# power.net
KiCad netlist of a schematic drawn in Altium Designer
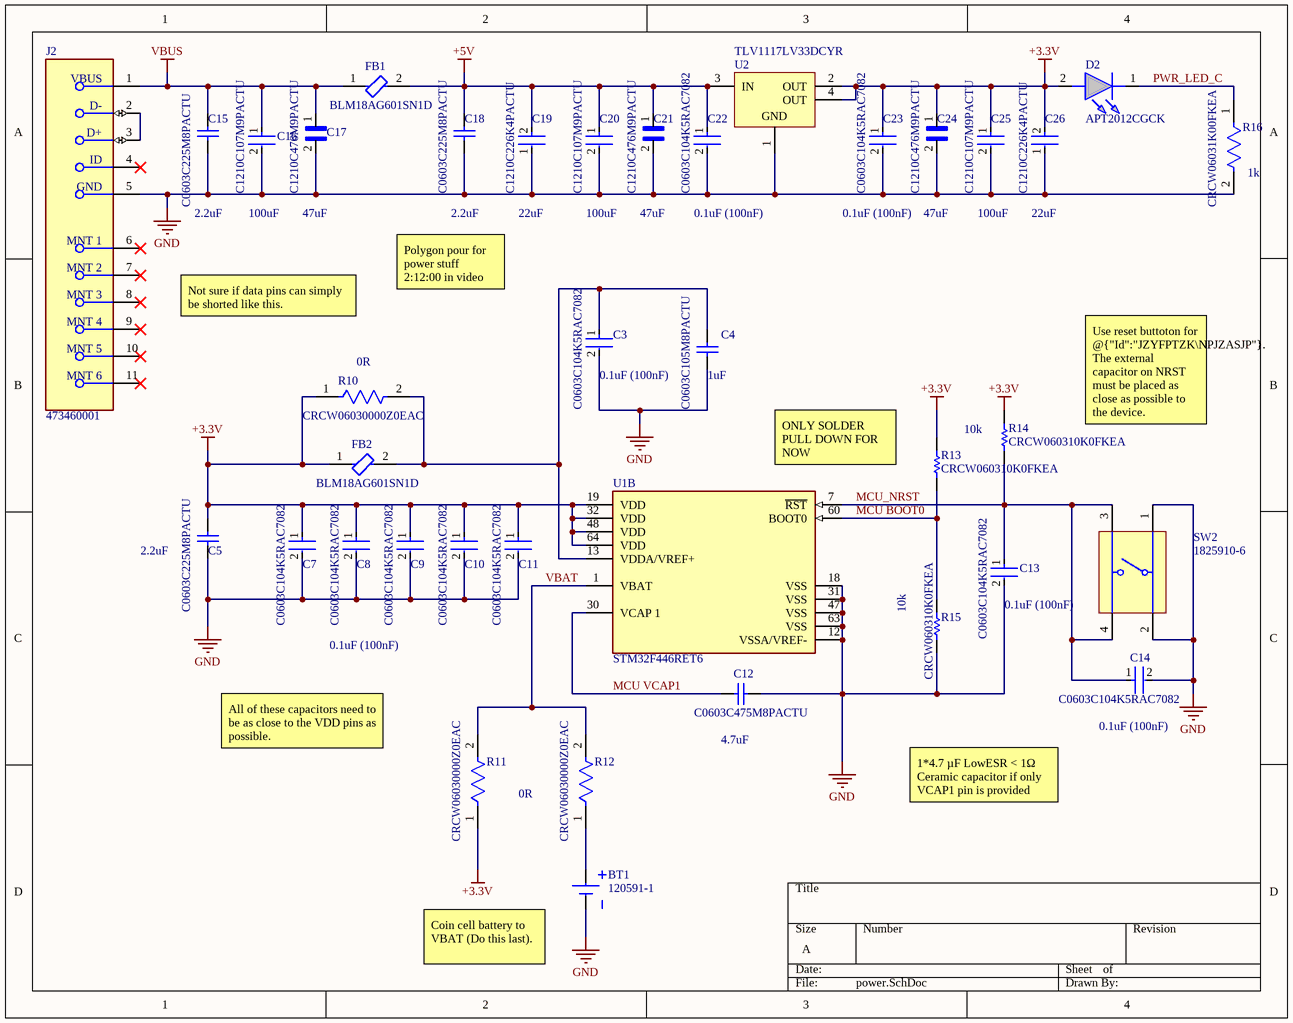
[diagram p0: power.SchDoc]

(export (version "E")
  (design (tool "Eeschema 10.0.6"))
  (components
    (comp (ref "BT1")
      (value "120591-1")
      (footprint "TECO-120591-1-2_V")
      (description "Lithium Battery Holder for CR2032 3V Cell")
      (fields (field (name "MANUFACTURER") "TE Connectivity"))
      (libsource (lib "Altium Content Vault") (part "TECO-120591-1-2"))
    )
    (comp (ref "C3")
      (value "C0603C104K5RAC7082")
      (footprint "FP-C0603C-CF-MFG")
      (description "C0603 0.10 μF X7R 30ppm/°C 10.00% 50 V")
      (fields
        (field (name "OCTOPART") "https://octopart.com/c0603c104k5rac7082-kemet-75146597")
        (field (name "MANUFACTURER") "KEMET")
      )
      (libsource (lib "Altium Content Vault") (part "b4654b650e69147ec39a6b967a45e02"))
    )
    (comp (ref "C4")
      (value "C0603C105M8PACTU")
      (footprint "CAPC1608X90X35LL15T15")
      (fields (field (name "MANUFACTURER") "Kemet"))
      (libsource (lib "Altium Content Vault") (part "CAP"))
    )
    (comp (ref "C5")
      (value "C0603C225M8PACTU")
      (footprint "CAPC1608X90X35LL15T15")
      (fields (field (name "MANUFACTURER") "Kemet"))
      (libsource (lib "Altium Content Vault") (part "CAP"))
    )
    (comp (ref "C7")
      (value "C0603C104K5RAC7082")
      (footprint "FP-C0603C-CF-MFG")
      (description "C0603 0.10 μF X7R 30ppm/°C 10.00% 50 V")
      (fields
        (field (name "OCTOPART") "https://octopart.com/c0603c104k5rac7082-kemet-75146597")
        (field (name "MANUFACTURER") "KEMET")
      )
      (libsource (lib "Altium Content Vault") (part "b4654b650e69147ec39a6b967a45e02"))
    )
    (comp (ref "C8")
      (value "C0603C104K5RAC7082")
      (footprint "FP-C0603C-CF-MFG")
      (description "C0603 0.10 μF X7R 30ppm/°C 10.00% 50 V")
      (fields
        (field (name "OCTOPART") "https://octopart.com/c0603c104k5rac7082-kemet-75146597")
        (field (name "MANUFACTURER") "KEMET")
      )
      (libsource (lib "Altium Content Vault") (part "b4654b650e69147ec39a6b967a45e02"))
    )
    (comp (ref "C9")
      (value "C0603C104K5RAC7082")
      (footprint "FP-C0603C-CF-MFG")
      (description "C0603 0.10 μF X7R 30ppm/°C 10.00% 50 V")
      (fields
        (field (name "OCTOPART") "https://octopart.com/c0603c104k5rac7082-kemet-75146597")
        (field (name "MANUFACTURER") "KEMET")
      )
      (libsource (lib "Altium Content Vault") (part "b4654b650e69147ec39a6b967a45e02"))
    )
    (comp (ref "C10")
      (value "C0603C104K5RAC7082")
      (footprint "FP-C0603C-CF-MFG")
      (description "C0603 0.10 μF X7R 30ppm/°C 10.00% 50 V")
      (fields
        (field (name "OCTOPART") "https://octopart.com/c0603c104k5rac7082-kemet-75146597")
        (field (name "MANUFACTURER") "KEMET")
      )
      (libsource (lib "Altium Content Vault") (part "b4654b650e69147ec39a6b967a45e02"))
    )
    (comp (ref "C11")
      (value "C0603C104K5RAC7082")
      (footprint "FP-C0603C-CF-MFG")
      (description "C0603 0.10 μF X7R 30ppm/°C 10.00% 50 V")
      (fields
        (field (name "OCTOPART") "https://octopart.com/c0603c104k5rac7082-kemet-75146597")
        (field (name "MANUFACTURER") "KEMET")
      )
      (libsource (lib "Altium Content Vault") (part "b4654b650e69147ec39a6b967a45e02"))
    )
    (comp (ref "C12")
      (value "C0603C475M8PACTU")
      (footprint "CAPC1608X90X35ML15T15")
      (fields (field (name "MANUFACTURER") "Kemet"))
      (libsource (lib "Altium Content Vault") (part "CAP"))
    )
    (comp (ref "C13")
      (value "C0603C104K5RAC7082")
      (footprint "FP-C0603C-CF-MFG")
      (description "C0603 0.10 μF X7R 30ppm/°C 10.00% 50 V")
      (fields
        (field (name "OCTOPART") "https://octopart.com/c0603c104k5rac7082-kemet-75146597")
        (field (name "MANUFACTURER") "KEMET")
      )
      (libsource (lib "Altium Content Vault") (part "b4654b650e69147ec39a6b967a45e02"))
    )
    (comp (ref "C14")
      (value "C0603C104K5RAC7082")
      (footprint "FP-C0603C-CF-MFG")
      (description "C0603 0.10 μF X7R 30ppm/°C 10.00% 50 V")
      (fields
        (field (name "OCTOPART") "https://octopart.com/c0603c104k5rac7082-kemet-75146597")
        (field (name "MANUFACTURER") "KEMET")
      )
      (libsource (lib "Altium Content Vault") (part "b4654b650e69147ec39a6b967a45e02"))
    )
    (comp (ref "C15")
      (value "C0603C225M8PACTU")
      (footprint "CAPC1608X90X35LL15T15")
      (fields (field (name "MANUFACTURER") "Kemet"))
      (libsource (lib "Altium Content Vault") (part "CAP"))
    )
    (comp (ref "C16")
      (value "C1210C107M9PACTU")
      (footprint "FP-C1210C107M9PACTU-MFG")
      (description "CAP CER 100UF 6.3V X5R 1210")
      (fields (field (name "VOLTAGE") "6.3V") (field (name "TOLERANCE") "20%"))
      (libsource (lib "Altium Content Vault") (part "b4654b650e69147ec39a6b967a45e02"))
    )
    (comp (ref "C17")
      (value "C1210C476M9PACTU")
      (footprint "CAPC3225X280")
      (description "CAP, MLCC, X5R, 47UF, 6.3V, 1210")
      (libsource (lib "C1210C476M9PACTU") (part "C1210C476M9PACTU"))
    )
    (comp (ref "C18")
      (value "C0603C225M8PACTU")
      (footprint "CAPC1608X90X35LL15T15")
      (fields (field (name "MANUFACTURER") "Kemet"))
      (libsource (lib "Altium Content Vault") (part "CAP"))
    )
    (comp (ref "C19")
      (value "C1210C226K4PACTU")
      (footprint "FP-C1210C226K4PACTU-MFG")
      (description "CAP CER 22UF 16V X5R 1210")
      (fields (field (name "VOLTAGE") "16V") (field (name "TOLERANCE") "10%"))
      (libsource (lib "Altium Content Vault") (part "236180d848d6139a670b325ea6854c9"))
    )
    (comp (ref "C20")
      (value "C1210C107M9PACTU")
      (footprint "FP-C1210C107M9PACTU-MFG")
      (description "CAP CER 100UF 6.3V X5R 1210")
      (fields (field (name "VOLTAGE") "6.3V") (field (name "TOLERANCE") "20%"))
      (libsource (lib "Altium Content Vault") (part "b4654b650e69147ec39a6b967a45e02"))
    )
    (comp (ref "C21")
      (value "C1210C476M9PACTU")
      (footprint "CAPC3225X280")
      (description "CAP, MLCC, X5R, 47UF, 6.3V, 1210")
      (libsource (lib "C1210C476M9PACTU") (part "C1210C476M9PACTU"))
    )
    (comp (ref "C22")
      (value "C0603C104K5RAC7082")
      (footprint "FP-C0603C-CF-MFG")
      (description "C0603 0.10 μF X7R 30ppm/°C 10.00% 50 V")
      (fields
        (field (name "OCTOPART") "https://octopart.com/c0603c104k5rac7082-kemet-75146597")
        (field (name "MANUFACTURER") "KEMET")
      )
      (libsource (lib "Altium Content Vault") (part "b4654b650e69147ec39a6b967a45e02"))
    )
    (comp (ref "C23")
      (value "C0603C104K5RAC7082")
      (footprint "FP-C0603C-CF-MFG")
      (description "C0603 0.10 μF X7R 30ppm/°C 10.00% 50 V")
      (fields
        (field (name "OCTOPART") "https://octopart.com/c0603c104k5rac7082-kemet-75146597")
        (field (name "MANUFACTURER") "KEMET")
      )
      (libsource (lib "Altium Content Vault") (part "b4654b650e69147ec39a6b967a45e02"))
    )
    (comp (ref "C24")
      (value "C1210C476M9PACTU")
      (footprint "CAPC3225X280")
      (description "CAP, MLCC, X5R, 47UF, 6.3V, 1210")
      (libsource (lib "C1210C476M9PACTU") (part "C1210C476M9PACTU"))
    )
    (comp (ref "C25")
      (value "C1210C107M9PACTU")
      (footprint "FP-C1210C107M9PACTU-MFG")
      (description "CAP CER 100UF 6.3V X5R 1210")
      (fields (field (name "VOLTAGE") "6.3V") (field (name "TOLERANCE") "20%"))
      (libsource (lib "Altium Content Vault") (part "b4654b650e69147ec39a6b967a45e02"))
    )
    (comp (ref "C26")
      (value "C1210C226K4PACTU")
      (footprint "FP-C1210C226K4PACTU-MFG")
      (description "CAP CER 22UF 16V X5R 1210")
      (fields (field (name "VOLTAGE") "16V") (field (name "TOLERANCE") "10%"))
      (libsource (lib "Altium Content Vault") (part "236180d848d6139a670b325ea6854c9"))
    )
    (comp (ref "D2")
      (value "APT2012CGCK")
      (footprint "LEDC2012X50N")
      (fields (field (name "MOUSER PART NUMBER") "604-APT2012CGCK"))
      (libsource (lib "APT2012CGCK") (part "APT2012CGCK"))
    )
    (comp (ref "FB1")
      (value "BLM18AG601SN1D")
      (footprint "FP-BLM18-0_15-t0_8-MFG")
      (description "Chip Ferrite Bead, 0603, 600Ω @ 100MHz, 0.38Ω, 25%, 500mA")
      (fields (field (name "TOLERANCE") "25%"))
      (libsource (lib "Altium Content Vault") (part "5f30dd21d616792df468990f7003faa"))
    )
    (comp (ref "FB2")
      (value "BLM18AG601SN1D")
      (footprint "FP-BLM18-0_15-t0_8-MFG")
      (description "Chip Ferrite Bead, 0603, 600Ω @ 100MHz, 0.38Ω, 25%, 500mA")
      (fields (field (name "TOLERANCE") "25%"))
      (libsource (lib "Altium Content Vault") (part "5f30dd21d616792df468990f7003faa"))
    )
    (comp (ref "J2")
      (value "473460001")
      (footprint "FP-473460001-MFG")
      (description "CONN RCPT USB2.0 MICRO B SMD R/A")
      (fields
        (field (name "OCTOPART") "https://octopart.com/47346-0001-molex-7164928")
        (field (name "MANUFACTURER") "Molex")
      )
      (libsource (lib "Altium Content Vault") (part "53ae1f1d9b557310b43ca686e5bb76a"))
    )
    (comp (ref "R10")
      (value "CRCW06030000Z0EAC")
      (footprint "FP-CRCW0603-C-IPC_B")
      (description "RES 0 OHM JUMPER 1/10W 0603")
      (libsource (lib "Altium Content Vault") (part "1029c3af85768c4190bb7ad29bc67b5"))
    )
    (comp (ref "R11")
      (value "CRCW06030000Z0EAC")
      (footprint "FP-CRCW0603-C-IPC_B")
      (description "RES 0 OHM JUMPER 1/10W 0603")
      (libsource (lib "Altium Content Vault") (part "1029c3af85768c4190bb7ad29bc67b5"))
    )
    (comp (ref "R12")
      (value "CRCW06030000Z0EAC")
      (footprint "FP-CRCW0603-C-IPC_B")
      (description "RES 0 OHM JUMPER 1/10W 0603")
      (libsource (lib "Altium Content Vault") (part "1029c3af85768c4190bb7ad29bc67b5"))
    )
    (comp (ref "R13")
      (value "CRCW060310K0FKEA")
      (footprint "RESC1609X50X30NL8T20")
      (description "Chip Resistor, 10 KOhm, +/- 1%, 100 mW, -55 to 155 degC, 0603 (1608 Metric), RoHS, Tape and Reel")
      (fields (field (name "MANUFACTURER") "Vishay Semiconductor"))
      (libsource (lib "Altium Content Vault") (part "RES-2"))
    )
    (comp (ref "R14")
      (value "CRCW060310K0FKEA")
      (footprint "RESC1609X50X30NL8T20")
      (description "Chip Resistor, 10 KOhm, +/- 1%, 100 mW, -55 to 155 degC, 0603 (1608 Metric), RoHS, Tape and Reel")
      (fields (field (name "MANUFACTURER") "Vishay Semiconductor"))
      (libsource (lib "Altium Content Vault") (part "RES-2"))
    )
    (comp (ref "R15")
      (value "CRCW060310K0FKEA")
      (footprint "RESC1609X50X30NL8T20")
      (description "Chip Resistor, 10 KOhm, +/- 1%, 100 mW, -55 to 155 degC, 0603 (1608 Metric), RoHS, Tape and Reel")
      (fields (field (name "MANUFACTURER") "Vishay Semiconductor"))
      (libsource (lib "Altium Content Vault") (part "RES-2"))
    )
    (comp (ref "R16")
      (value "CRCW06031K00FKEA")
      (footprint "FP-CRCW0603-e3-MFG")
      (description "RES Thick Film, 1kΩ, 1%, 0.1W, 100ppm/°C, 0603")
      (fields (field (name "TOLERANCE") "1%"))
      (libsource (lib "Altium Content Vault") (part "1029c3af85768c4190bb7ad29bc67b5"))
    )
    (comp (ref "SW2")
      (value "1825910-6")
      (footprint "TECO-1825910-6_V")
      (description "Tact Switch, SPST-NO, 0.05 A, -35 to 85 degC, 4-Pin THD, RoHS, Bulk")
      (fields (field (name "MANUFACTURER") "TE Connectivity"))
      (libsource (lib "Altium Content Vault") (part "SW-SPST-4_A"))
    )
    (comp (ref "U1")
      (value "STM32F446RET6")
      (footprint "FP-LQFP64-5W-MFG")
      (description "IC MCU 32BIT 512KB FLASH 64LQFP")
      (fields
        (field (name "OCTOPART") "https://octopart.com/stm32f446ret6-stmicroelectronics-52642920")
        (field (name "MANUFACTURER") "ST")
      )
      (libsource (lib "Altium Content Vault") (part "ee11adc32c0ab33b933cccf4348c338"))
    )
    (comp (ref "U2")
      (value "TLV1117LV33DCYR")
      (footprint "DCY0004A_N")
      (fields (field (name "MANUFACTURER") "Texas Instruments"))
      (libsource (lib "Altium Content Vault") (part "TI-TLV1117LV33DCY4"))
    )
  )
  (nets
    (net (code "1") (name "+3.3V") (class "Default")
      (node (ref "C10") (pin "1") (pinfunction "1_1") (pintype "passive"))
      (node (ref "C11") (pin "1") (pinfunction "1_1") (pintype "passive"))
      (node (ref "C23") (pin "1") (pinfunction "1_1") (pintype "passive"))
      (node (ref "C24") (pin "1") (pinfunction "1_1") (pintype "passive"))
      (node (ref "C25") (pin "1") (pinfunction "1_1") (pintype "passive"))
      (node (ref "C26") (pin "2") (pinfunction "2_2") (pintype "passive"))
      (node (ref "C5") (pin "1") (pinfunction "1_1") (pintype "passive"))
      (node (ref "C7") (pin "1") (pinfunction "1_1") (pintype "passive"))
      (node (ref "C8") (pin "1") (pinfunction "1_1") (pintype "passive"))
      (node (ref "C9") (pin "1") (pinfunction "1_1") (pintype "passive"))
      (node (ref "D2") (pin "2") (pinfunction "A_2") (pintype "passive"))
      (node (ref "FB2") (pin "1") (pinfunction "1_1") (pintype "passive"))
      (node (ref "R10") (pin "1") (pinfunction "1_1") (pintype "passive"))
      (node (ref "R11") (pin "1") (pinfunction "1_1") (pintype "passive"))
      (node (ref "R13") (pin "2") (pinfunction "2_2") (pintype "passive"))
      (node (ref "R14") (pin "2") (pinfunction "2_2") (pintype "passive"))
      (node (ref "U1") (pin "19") (pinfunction "VDD_19") (pintype "power_in"))
      (node (ref "U1") (pin "32") (pinfunction "VDD_32") (pintype "power_in"))
      (node (ref "U1") (pin "48") (pinfunction "VDD_48") (pintype "power_in"))
      (node (ref "U1") (pin "64") (pinfunction "VDD_64") (pintype "power_in"))
      (node (ref "U2") (pin "2") (pinfunction "OUT_2") (pintype "power_in"))
      (node (ref "U2") (pin "4") (pinfunction "OUT_4") (pintype "power_in"))
    )
    (net (code "2") (name "+5V") (class "Default")
      (node (ref "C18") (pin "1") (pinfunction "1_1") (pintype "passive"))
      (node (ref "C19") (pin "2") (pinfunction "2_2") (pintype "passive"))
      (node (ref "C20") (pin "1") (pinfunction "1_1") (pintype "passive"))
      (node (ref "C21") (pin "1") (pinfunction "1_1") (pintype "passive"))
      (node (ref "C22") (pin "1") (pinfunction "1_1") (pintype "passive"))
      (node (ref "FB1") (pin "2") (pinfunction "2_2") (pintype "passive"))
      (node (ref "U2") (pin "3") (pinfunction "IN_3") (pintype "power_in"))
    )
    (net (code "3") (name "/MCU BOOT0") (class "Default")
      (node (ref "R13") (pin "1") (pinfunction "1_1") (pintype "passive"))
      (node (ref "R15") (pin "2") (pinfunction "2_2") (pintype "passive"))
      (node (ref "U1") (pin "60") (pinfunction "BOOT0_60") (pintype "input"))
    )
    (net (code "4") (name "/MCU VCAP1") (class "Default")
      (node (ref "C12") (pin "1") (pinfunction "1_1") (pintype "passive"))
      (node (ref "U1") (pin "30") (pinfunction "VCAP_1_30") (pintype "power_in"))
    )
    (net (code "5") (name "/MCU_NRST") (class "Default")
      (node (ref "C13") (pin "1") (pinfunction "1_1") (pintype "passive"))
      (node (ref "C14") (pin "1") (pinfunction "1_1") (pintype "passive"))
      (node (ref "R14") (pin "1") (pinfunction "1_1") (pintype "passive"))
      (node (ref "SW2") (pin "3") (pinfunction "3_3") (pintype "passive"))
      (node (ref "SW2") (pin "4") (pinfunction "4_4") (pintype "passive"))
      (node (ref "U1") (pin "7") (pinfunction "~{RST}_7") (pintype "input"))
    )
    (net (code "6") (name "/PWR_LED_C") (class "Default")
      (node (ref "D2") (pin "1") (pinfunction "K_1") (pintype "passive"))
      (node (ref "R16") (pin "1") (pinfunction "1_1") (pintype "passive"))
    )
    (net (code "7") (name "/VBAT") (class "Default")
      (node (ref "R11") (pin "2") (pinfunction "2_2") (pintype "passive"))
      (node (ref "R12") (pin "2") (pinfunction "2_2") (pintype "passive"))
      (node (ref "U1") (pin "1") (pinfunction "VBAT_1") (pintype "power_in"))
    )
    (net (code "8") (name "GND") (class "Default")
      (node (ref "BT1") (pin "2") (pinfunction "-_2") (pintype "passive"))
      (node (ref "C10") (pin "2") (pinfunction "2_2") (pintype "passive"))
      (node (ref "C11") (pin "2") (pinfunction "2_2") (pintype "passive"))
      (node (ref "C12") (pin "2") (pinfunction "2_2") (pintype "passive"))
      (node (ref "C13") (pin "2") (pinfunction "2_2") (pintype "passive"))
      (node (ref "C14") (pin "2") (pinfunction "2_2") (pintype "passive"))
      (node (ref "C15") (pin "2") (pinfunction "2_2") (pintype "passive"))
      (node (ref "C16") (pin "2") (pinfunction "2_2") (pintype "passive"))
      (node (ref "C17") (pin "2") (pinfunction "2_2") (pintype "passive"))
      (node (ref "C18") (pin "2") (pinfunction "2_2") (pintype "passive"))
      (node (ref "C19") (pin "1") (pinfunction "1_1") (pintype "passive"))
      (node (ref "C20") (pin "2") (pinfunction "2_2") (pintype "passive"))
      (node (ref "C21") (pin "2") (pinfunction "2_2") (pintype "passive"))
      (node (ref "C22") (pin "2") (pinfunction "2_2") (pintype "passive"))
      (node (ref "C23") (pin "2") (pinfunction "2_2") (pintype "passive"))
      (node (ref "C24") (pin "2") (pinfunction "2_2") (pintype "passive"))
      (node (ref "C25") (pin "2") (pinfunction "2_2") (pintype "passive"))
      (node (ref "C26") (pin "1") (pinfunction "1_1") (pintype "passive"))
      (node (ref "C3") (pin "2") (pinfunction "2_2") (pintype "passive"))
      (node (ref "C4") (pin "1") (pinfunction "1_1") (pintype "passive"))
      (node (ref "C5") (pin "2") (pinfunction "2_2") (pintype "passive"))
      (node (ref "C7") (pin "2") (pinfunction "2_2") (pintype "passive"))
      (node (ref "C8") (pin "2") (pinfunction "2_2") (pintype "passive"))
      (node (ref "C9") (pin "2") (pinfunction "2_2") (pintype "passive"))
      (node (ref "J2") (pin "5") (pinfunction "GND_5") (pintype "power_in"))
      (node (ref "R15") (pin "1") (pinfunction "1_1") (pintype "passive"))
      (node (ref "R16") (pin "2") (pinfunction "2_2") (pintype "passive"))
      (node (ref "SW2") (pin "1") (pinfunction "1_1") (pintype "passive"))
      (node (ref "SW2") (pin "2") (pinfunction "2_2") (pintype "passive"))
      (node (ref "U1") (pin "12") (pinfunction "VSSA/VREF-_12") (pintype "power_in"))
      (node (ref "U1") (pin "18") (pinfunction "VSS_18") (pintype "power_in"))
      (node (ref "U1") (pin "31") (pinfunction "VSS_31") (pintype "power_in"))
      (node (ref "U1") (pin "47") (pinfunction "VSS_47") (pintype "power_in"))
      (node (ref "U1") (pin "63") (pinfunction "VSS_63") (pintype "power_in"))
      (node (ref "U2") (pin "1") (pinfunction "GND_1") (pintype "power_in"))
    )
    (net (code "9") (name "Net-(BT1-+)") (class "Default")
      (node (ref "BT1") (pin "1") (pinfunction "+_1") (pintype "passive"))
      (node (ref "R12") (pin "1") (pinfunction "1_1") (pintype "passive"))
    )
    (net (code "10") (name "Net-(J2-D+)") (class "Default")
      (node (ref "J2") (pin "2") (pinfunction "D-_2") (pintype "bidirectional"))
      (node (ref "J2") (pin "3") (pinfunction "D+_3") (pintype "bidirectional"))
    )
    (net (code "11") (name "Net-(U1B-VDDA{slash}VREF+)") (class "Default")
      (node (ref "C3") (pin "1") (pinfunction "1_1") (pintype "passive"))
      (node (ref "C4") (pin "2") (pinfunction "2_2") (pintype "passive"))
      (node (ref "FB2") (pin "2") (pinfunction "2_2") (pintype "passive"))
      (node (ref "R10") (pin "2") (pinfunction "2_2") (pintype "passive"))
      (node (ref "U1") (pin "13") (pinfunction "VDDA/VREF+_13") (pintype "power_in"))
    )
    (net (code "12") (name "VBUS") (class "Default")
      (node (ref "C15") (pin "1") (pinfunction "1_1") (pintype "passive"))
      (node (ref "C16") (pin "1") (pinfunction "1_1") (pintype "passive"))
      (node (ref "C17") (pin "1") (pinfunction "1_1") (pintype "passive"))
      (node (ref "FB1") (pin "1") (pinfunction "1_1") (pintype "passive"))
      (node (ref "J2") (pin "1") (pinfunction "VBUS_1") (pintype "power_in"))
    )
    (net (code "13") (name "unconnected-(J2-ID-Pad4)") (class "Default")
      (node (ref "J2") (pin "4") (pinfunction "ID_4") (pintype "passive+no_connect"))
    )
    (net (code "14") (name "unconnected-(J2-MNT_1-Pad6)") (class "Default")
      (node (ref "J2") (pin "6") (pinfunction "MNT_1_6") (pintype "passive+no_connect"))
    )
    (net (code "15") (name "unconnected-(J2-MNT_2-Pad7)") (class "Default")
      (node (ref "J2") (pin "7") (pinfunction "MNT_2_7") (pintype "passive+no_connect"))
    )
    (net (code "16") (name "unconnected-(J2-MNT_3-Pad8)") (class "Default")
      (node (ref "J2") (pin "8") (pinfunction "MNT_3_8") (pintype "passive+no_connect"))
    )
    (net (code "17") (name "unconnected-(J2-MNT_4-Pad9)") (class "Default")
      (node (ref "J2") (pin "9") (pinfunction "MNT_4_9") (pintype "passive+no_connect"))
    )
    (net (code "18") (name "unconnected-(J2-MNT_5-Pad10)") (class "Default")
      (node (ref "J2") (pin "10") (pinfunction "MNT_5_10") (pintype "passive+no_connect"))
    )
    (net (code "19") (name "unconnected-(J2-MNT_6-Pad11)") (class "Default")
      (node (ref "J2") (pin "11") (pinfunction "MNT_6_11") (pintype "passive+no_connect"))
    )
  )
)
